# Bmp180Shield.net
KiCad netlist of a schematic drawn in EAGLE
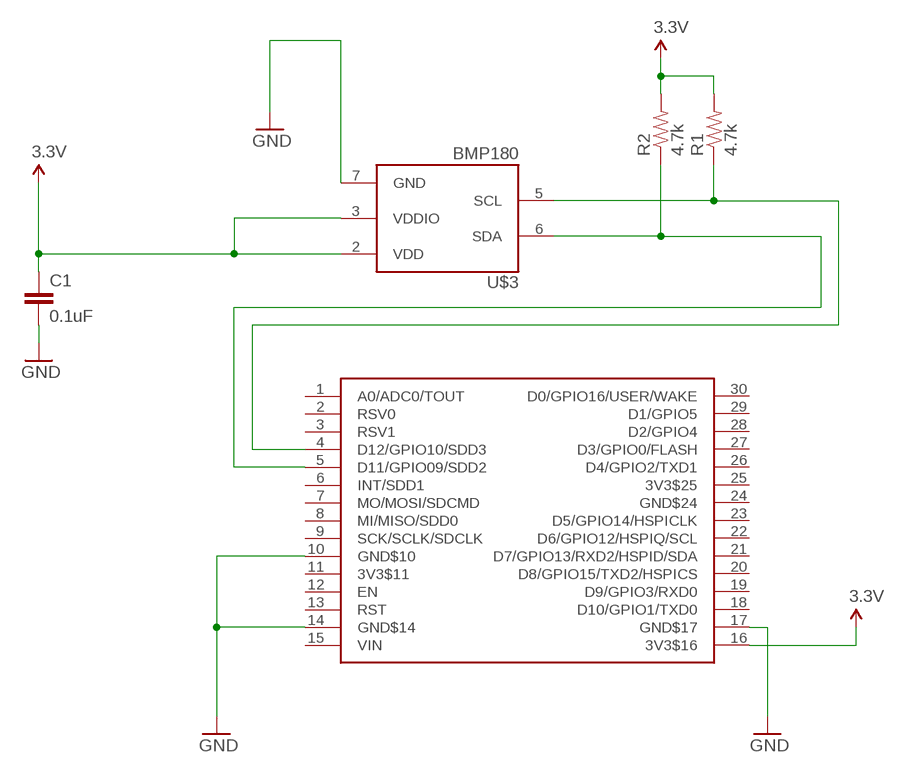
[diagram p0: schematic, sheet 1]

(export (version "E")
  (design (tool "Eeschema 10.0.6"))
  (components
    (comp (ref "C1")
      (value "0.1uF")
      (footprint "eagle-import:0402-CAP")
      (libsource (lib "eagle-import") (part "CAP0402-CAP"))
    )
    (comp (ref "R1")
      (value "4.7k")
      (footprint "eagle-import:0402-RES")
      (libsource (lib "eagle-import") (part "RESISTOR0402-RES"))
    )
    (comp (ref "R2")
      (value "4.7k")
      (footprint "eagle-import:0402-RES")
      (libsource (lib "eagle-import") (part "RESISTOR0402-RES"))
    )
    (comp (ref "U$1")
      (value "NERDSHIELD")
      (footprint "eagle-import:NERDUINO_STACK")
      (libsource (lib "eagle-import") (part "NERDSHIELD"))
    )
    (comp (ref "U$3")
      (value "BMP180")
      (footprint "eagle-import:BMP180")
      (libsource (lib "eagle-import") (part "BMP180"))
    )
  )
  (nets
    (net (code "1") (name "3.3V") (class "Default")
      (node (ref "C1") (pin "1") (pinfunction "1_1") (pintype "passive"))
      (node (ref "R1") (pin "2") (pinfunction "2_2") (pintype "passive"))
      (node (ref "R2") (pin "2") (pinfunction "2_2") (pintype "passive"))
      (node (ref "U$1") (pin "16") (pinfunction "3V3$16_16") (pintype "bidirectional"))
      (node (ref "U$3") (pin "2") (pinfunction "VDD_2") (pintype "power_in"))
      (node (ref "U$3") (pin "3") (pinfunction "VDDIO_3") (pintype "power_in"))
    )
    (net (code "2") (name "GND") (class "Default")
      (node (ref "C1") (pin "2") (pinfunction "2_2") (pintype "passive"))
      (node (ref "U$1") (pin "10") (pinfunction "GND$10_10") (pintype "bidirectional"))
      (node (ref "U$1") (pin "14") (pinfunction "GND$14_14") (pintype "bidirectional"))
      (node (ref "U$1") (pin "17") (pinfunction "GND$17_17") (pintype "bidirectional"))
      (node (ref "U$3") (pin "7") (pinfunction "GND_7") (pintype "power_in"))
    )
    (net (code "3") (name "Net-(U$1-D11{slash}GPIO09{slash}SDD2)") (class "Default")
      (node (ref "R2") (pin "1") (pinfunction "1_1") (pintype "passive"))
      (node (ref "U$1") (pin "5") (pinfunction "D11/GPIO09/SDD2_5") (pintype "bidirectional"))
      (node (ref "U$3") (pin "6") (pinfunction "SDA_6") (pintype "bidirectional"))
    )
    (net (code "4") (name "Net-(U$1-D12{slash}GPIO10{slash}SDD3)") (class "Default")
      (node (ref "R1") (pin "1") (pinfunction "1_1") (pintype "passive"))
      (node (ref "U$1") (pin "4") (pinfunction "D12/GPIO10/SDD3_4") (pintype "bidirectional"))
      (node (ref "U$3") (pin "5") (pinfunction "SCL_5") (pintype "input"))
    )
    (net (code "5") (name "unconnected-(U$1-3V3$11-Pad11)") (class "Default")
      (node (ref "U$1") (pin "11") (pinfunction "3V3$11_11") (pintype "bidirectional"))
    )
    (net (code "6") (name "unconnected-(U$1-3V3$25-Pad25)") (class "Default")
      (node (ref "U$1") (pin "25") (pinfunction "3V3$25_25") (pintype "bidirectional"))
    )
    (net (code "7") (name "unconnected-(U$1-A0{slash}ADC0{slash}TOUT-Pad1)") (class "Default")
      (node (ref "U$1") (pin "1") (pinfunction "A0/ADC0/TOUT_1") (pintype "bidirectional"))
    )
    (net (code "8") (name "unconnected-(U$1-D0{slash}GPIO16{slash}USER{slash}WAKE-Pad30)") (class "Default")
      (node (ref "U$1") (pin "30") (pinfunction "D0/GPIO16/USER/WAKE_30") (pintype "bidirectional"))
    )
    (net (code "9") (name "unconnected-(U$1-D1{slash}GPIO5-Pad29)") (class "Default")
      (node (ref "U$1") (pin "29") (pinfunction "D1/GPIO5_29") (pintype "bidirectional"))
    )
    (net (code "10") (name "unconnected-(U$1-D2{slash}GPIO4-Pad28)") (class "Default")
      (node (ref "U$1") (pin "28") (pinfunction "D2/GPIO4_28") (pintype "bidirectional"))
    )
    (net (code "11") (name "unconnected-(U$1-D3{slash}GPIO0{slash}FLASH-Pad27)") (class "Default")
      (node (ref "U$1") (pin "27") (pinfunction "D3/GPIO0/FLASH_27") (pintype "bidirectional"))
    )
    (net (code "12") (name "unconnected-(U$1-D4{slash}GPIO2{slash}TXD1-Pad26)") (class "Default")
      (node (ref "U$1") (pin "26") (pinfunction "D4/GPIO2/TXD1_26") (pintype "bidirectional"))
    )
    (net (code "13") (name "unconnected-(U$1-D5{slash}GPIO14{slash}HSPICLK-Pad23)") (class "Default")
      (node (ref "U$1") (pin "23") (pinfunction "D5/GPIO14/HSPICLK_23") (pintype "bidirectional"))
    )
    (net (code "14") (name "unconnected-(U$1-D6{slash}GPIO12{slash}HSPIQ{slash}SCL-Pad22)") (class "Default")
      (node (ref "U$1") (pin "22") (pinfunction "D6/GPIO12/HSPIQ/SCL_22") (pintype "bidirectional"))
    )
    (net (code "15") (name "unconnected-(U$1-D7{slash}GPIO13{slash}RXD2{slash}HSPID{slash}SDA-Pad21)") (class "Default")
      (node (ref "U$1") (pin "21") (pinfunction "D7/GPIO13/RXD2/HSPID/SDA_21") (pintype "bidirectional"))
    )
    (net (code "16") (name "unconnected-(U$1-D8{slash}GPIO15{slash}TXD2{slash}HSPICS-Pad20)") (class "Default")
      (node (ref "U$1") (pin "20") (pinfunction "D8/GPIO15/TXD2/HSPICS_20") (pintype "bidirectional"))
    )
    (net (code "17") (name "unconnected-(U$1-D9{slash}GPIO3{slash}RXD0-Pad19)") (class "Default")
      (node (ref "U$1") (pin "19") (pinfunction "D9/GPIO3/RXD0_19") (pintype "bidirectional"))
    )
    (net (code "18") (name "unconnected-(U$1-D10{slash}GPIO1{slash}TXD0-Pad18)") (class "Default")
      (node (ref "U$1") (pin "18") (pinfunction "D10/GPIO1/TXD0_18") (pintype "bidirectional"))
    )
    (net (code "19") (name "unconnected-(U$1-EN-Pad12)") (class "Default")
      (node (ref "U$1") (pin "12") (pinfunction "EN_12") (pintype "bidirectional"))
    )
    (net (code "20") (name "unconnected-(U$1-GND$24-Pad24)") (class "Default")
      (node (ref "U$1") (pin "24") (pinfunction "GND$24_24") (pintype "bidirectional"))
    )
    (net (code "21") (name "unconnected-(U$1-INT{slash}SDD1-Pad6)") (class "Default")
      (node (ref "U$1") (pin "6") (pinfunction "INT/SDD1_6") (pintype "bidirectional"))
    )
    (net (code "22") (name "unconnected-(U$1-MI{slash}MISO{slash}SDD0-Pad8)") (class "Default")
      (node (ref "U$1") (pin "8") (pinfunction "MI/MISO/SDD0_8") (pintype "bidirectional"))
    )
    (net (code "23") (name "unconnected-(U$1-MO{slash}MOSI{slash}SDCMD-Pad7)") (class "Default")
      (node (ref "U$1") (pin "7") (pinfunction "MO/MOSI/SDCMD_7") (pintype "bidirectional"))
    )
    (net (code "24") (name "unconnected-(U$1-RST-Pad13)") (class "Default")
      (node (ref "U$1") (pin "13") (pinfunction "RST_13") (pintype "bidirectional"))
    )
    (net (code "25") (name "unconnected-(U$1-RSV0-Pad2)") (class "Default")
      (node (ref "U$1") (pin "2") (pinfunction "RSV0_2") (pintype "bidirectional"))
    )
    (net (code "26") (name "unconnected-(U$1-RSV1-Pad3)") (class "Default")
      (node (ref "U$1") (pin "3") (pinfunction "RSV1_3") (pintype "bidirectional"))
    )
    (net (code "27") (name "unconnected-(U$1-SCK{slash}SCLK{slash}SDCLK-Pad9)") (class "Default")
      (node (ref "U$1") (pin "9") (pinfunction "SCK/SCLK/SDCLK_9") (pintype "bidirectional"))
    )
    (net (code "28") (name "unconnected-(U$1-VIN-Pad15)") (class "Default")
      (node (ref "U$1") (pin "15") (pinfunction "VIN_15") (pintype "bidirectional"))
    )
  )
)
